# powerCard_rev0_1.net
KiCad netlist of a schematic drawn in EAGLE
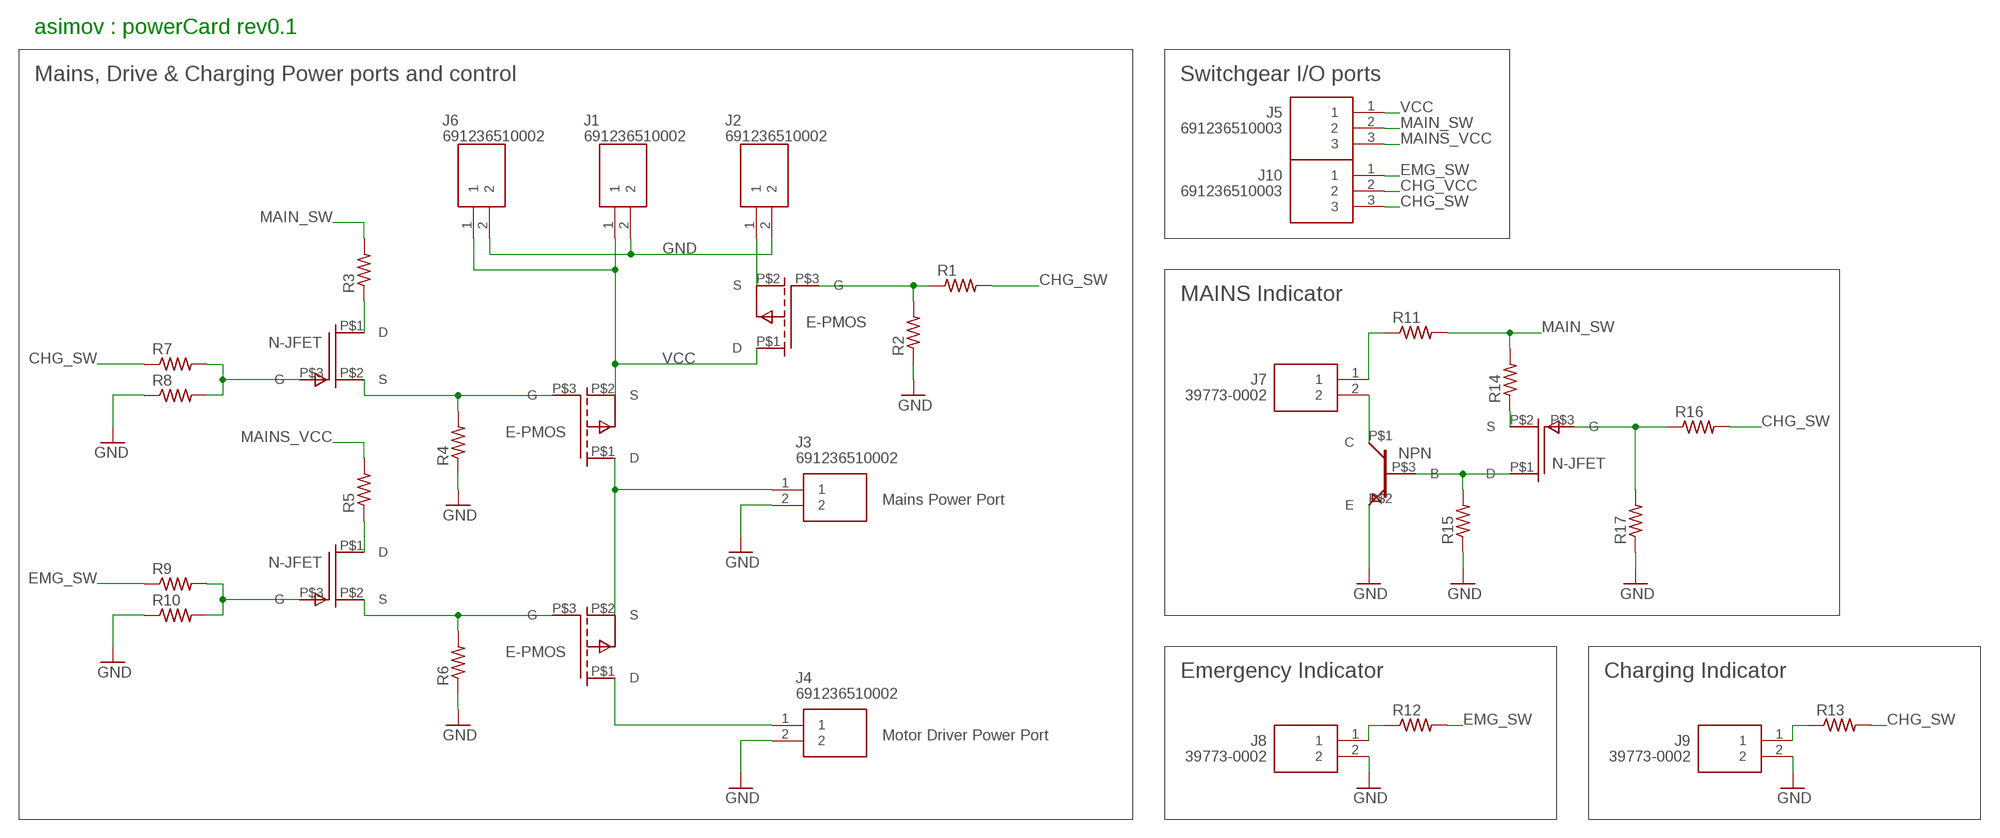
[diagram p0: schematic, sheet 1]

(export (version "E")
  (design (tool "Eeschema 10.0.6"))
  (components
    (comp (ref "J1")
      (value "691236510002")
      (footprint "eagle-import:SHDR2W90P0X508_1X2_1076X1135X1")
      (fields (field (name "MOUSER_PART_NUMBER") "710-691236510002"))
      (libsource (lib "eagle-import") (part "691236510002"))
    )
    (comp (ref "J2")
      (value "691236510002")
      (footprint "eagle-import:SHDR2W90P0X508_1X2_1076X1135X1")
      (fields (field (name "MOUSER_PART_NUMBER") "710-691236510002"))
      (libsource (lib "eagle-import") (part "691236510002"))
    )
    (comp (ref "J3")
      (value "691236510002")
      (footprint "eagle-import:SHDR2W90P0X508_1X2_1076X1135X1")
      (fields (field (name "MOUSER_PART_NUMBER") "710-691236510002"))
      (libsource (lib "eagle-import") (part "691236510002"))
    )
    (comp (ref "J4")
      (value "691236510002")
      (footprint "eagle-import:SHDR2W90P0X508_1X2_1076X1135X1")
      (fields (field (name "MOUSER_PART_NUMBER") "710-691236510002"))
      (libsource (lib "eagle-import") (part "691236510002"))
    )
    (comp (ref "J5")
      (value "691236510003")
      (footprint "eagle-import:SHDR3W90P0X508_1X3_1524X1135X1")
      (fields (field (name "MOUSER_PART_NUMBER") "710-691236510003"))
      (libsource (lib "eagle-import") (part "691236510003"))
    )
    (comp (ref "J6")
      (value "691236510002")
      (footprint "eagle-import:SHDR2W90P0X508_1X2_1076X1135X1")
      (fields (field (name "MOUSER_PART_NUMBER") "710-691236510002"))
      (libsource (lib "eagle-import") (part "691236510002"))
    )
    (comp (ref "J7")
      (value "39773-0002")
      (footprint "eagle-import:SHDR2W110P0X254_1X2_554X650X10")
      (fields (field (name "MOUSER_PART_NUMBER") "538-39773-0002"))
      (libsource (lib "eagle-import") (part "39773-0002"))
    )
    (comp (ref "J8")
      (value "39773-0002")
      (footprint "eagle-import:SHDR2W110P0X254_1X2_554X650X10")
      (fields (field (name "MOUSER_PART_NUMBER") "538-39773-0002"))
      (libsource (lib "eagle-import") (part "39773-0002"))
    )
    (comp (ref "J9")
      (value "39773-0002")
      (footprint "eagle-import:SHDR2W110P0X254_1X2_554X650X10")
      (fields (field (name "MOUSER_PART_NUMBER") "538-39773-0002"))
      (libsource (lib "eagle-import") (part "39773-0002"))
    )
    (comp (ref "J10")
      (value "691236510003")
      (footprint "eagle-import:SHDR3W90P0X508_1X3_1524X1135X1")
      (fields (field (name "MOUSER_PART_NUMBER") "710-691236510003"))
      (libsource (lib "eagle-import") (part "691236510003"))
    )
    (comp (ref "R1")
      (value "R-US_0204/7")
      (footprint "eagle-import:0204_7")
      (libsource (lib "eagle-import") (part "R-US_0204/7"))
    )
    (comp (ref "R2")
      (value "R-US_0204/7")
      (footprint "eagle-import:0204_7")
      (libsource (lib "eagle-import") (part "R-US_0204/7"))
    )
    (comp (ref "R3")
      (value "R-US_0204/7")
      (footprint "eagle-import:0204_7")
      (libsource (lib "eagle-import") (part "R-US_0204/7"))
    )
    (comp (ref "R4")
      (value "R-US_0204/7")
      (footprint "eagle-import:0204_7")
      (libsource (lib "eagle-import") (part "R-US_0204/7"))
    )
    (comp (ref "R5")
      (value "R-US_0204/7")
      (footprint "eagle-import:0204_7")
      (libsource (lib "eagle-import") (part "R-US_0204/7"))
    )
    (comp (ref "R6")
      (value "R-US_0204/7")
      (footprint "eagle-import:0204_7")
      (libsource (lib "eagle-import") (part "R-US_0204/7"))
    )
    (comp (ref "R7")
      (value "R-US_0204/7")
      (footprint "eagle-import:0204_7")
      (libsource (lib "eagle-import") (part "R-US_0204/7"))
    )
    (comp (ref "R8")
      (value "R-US_0204/7")
      (footprint "eagle-import:0204_7")
      (libsource (lib "eagle-import") (part "R-US_0204/7"))
    )
    (comp (ref "R9")
      (value "R-US_0204/7")
      (footprint "eagle-import:0204_7")
      (libsource (lib "eagle-import") (part "R-US_0204/7"))
    )
    (comp (ref "R10")
      (value "R-US_0204/7")
      (footprint "eagle-import:0204_7")
      (libsource (lib "eagle-import") (part "R-US_0204/7"))
    )
    (comp (ref "R11")
      (value "R-US_0204/7")
      (footprint "eagle-import:0204_7")
      (libsource (lib "eagle-import") (part "R-US_0204/7"))
    )
    (comp (ref "R12")
      (value "R-US_0204/7")
      (footprint "eagle-import:0204_7")
      (libsource (lib "eagle-import") (part "R-US_0204/7"))
    )
    (comp (ref "R13")
      (value "R-US_0204/7")
      (footprint "eagle-import:0204_7")
      (libsource (lib "eagle-import") (part "R-US_0204/7"))
    )
    (comp (ref "R14")
      (value "R-US_0204/7")
      (footprint "eagle-import:0204_7")
      (libsource (lib "eagle-import") (part "R-US_0204/7"))
    )
    (comp (ref "R15")
      (value "R-US_0204/7")
      (footprint "eagle-import:0204_7")
      (libsource (lib "eagle-import") (part "R-US_0204/7"))
    )
    (comp (ref "R16")
      (value "R-US_0204/7")
      (footprint "eagle-import:0204_7")
      (libsource (lib "eagle-import") (part "R-US_0204/7"))
    )
    (comp (ref "R17")
      (value "R-US_0204/7")
      (footprint "eagle-import:0204_7")
      (libsource (lib "eagle-import") (part "R-US_0204/7"))
    )
    (comp (ref "U$1")
      (value "E-PMOSFET")
      (footprint "eagle-import:TO-220")
      (libsource (lib "eagle-import") (part "E-PMOSFET"))
    )
    (comp (ref "U$2")
      (value "E-PMOSFET")
      (footprint "eagle-import:TO-220")
      (libsource (lib "eagle-import") (part "E-PMOSFET"))
    )
    (comp (ref "U$3")
      (value "E-PMOSFET")
      (footprint "eagle-import:TO-220")
      (libsource (lib "eagle-import") (part "E-PMOSFET"))
    )
    (comp (ref "U$4")
      (value "N-JFET")
      (footprint "eagle-import:TO-92(3L)")
      (libsource (lib "eagle-import") (part "N-JFET"))
    )
    (comp (ref "U$5")
      (value "N-JFET")
      (footprint "eagle-import:TO-92(3L)")
      (libsource (lib "eagle-import") (part "N-JFET"))
    )
    (comp (ref "U$6")
      (value "NPN-BJT")
      (footprint "eagle-import:TO-92")
      (libsource (lib "eagle-import") (part "NPN-BJT"))
    )
    (comp (ref "U$7")
      (value "N-JFET")
      (footprint "eagle-import:TO-92(3L)")
      (libsource (lib "eagle-import") (part "N-JFET"))
    )
  )
  (nets
    (net (code "1") (name "/CHG_SW") (class "Default")
      (node (ref "J10") (pin "3") (pinfunction "3_3") (pintype "bidirectional"))
      (node (ref "R1") (pin "2") (pinfunction "2_2") (pintype "passive"))
      (node (ref "R13") (pin "2") (pinfunction "2_2") (pintype "passive"))
      (node (ref "R16") (pin "2") (pinfunction "2_2") (pintype "passive"))
      (node (ref "R7") (pin "1") (pinfunction "1_1") (pintype "passive"))
    )
    (net (code "2") (name "/CHG_VCC") (class "Default")
      (node (ref "J10") (pin "2") (pinfunction "2_2") (pintype "bidirectional"))
      (node (ref "J2") (pin "1") (pinfunction "1_1") (pintype "bidirectional"))
      (node (ref "U$1") (pin "P$2") (pinfunction "S_P$2") (pintype "output"))
    )
    (net (code "3") (name "/EMG_SW") (class "Default")
      (node (ref "J10") (pin "1") (pinfunction "1_1") (pintype "bidirectional"))
      (node (ref "R12") (pin "2") (pinfunction "2_2") (pintype "passive"))
      (node (ref "R9") (pin "1") (pinfunction "1_1") (pintype "passive"))
    )
    (net (code "4") (name "/MAINS_VCC") (class "Default")
      (node (ref "J3") (pin "1") (pinfunction "1_1") (pintype "bidirectional"))
      (node (ref "J5") (pin "3") (pinfunction "3_3") (pintype "bidirectional"))
      (node (ref "R5") (pin "2") (pinfunction "2_2") (pintype "passive"))
      (node (ref "U$2") (pin "P$1") (pinfunction "D_P$1") (pintype "input"))
      (node (ref "U$3") (pin "P$2") (pinfunction "S_P$2") (pintype "output"))
    )
    (net (code "5") (name "/MAIN_SW") (class "Default")
      (node (ref "J5") (pin "2") (pinfunction "2_2") (pintype "bidirectional"))
      (node (ref "R11") (pin "2") (pinfunction "2_2") (pintype "passive"))
      (node (ref "R14") (pin "2") (pinfunction "2_2") (pintype "passive"))
      (node (ref "R3") (pin "2") (pinfunction "2_2") (pintype "passive"))
    )
    (net (code "6") (name "/VCC") (class "Default")
      (node (ref "J1") (pin "1") (pinfunction "1_1") (pintype "bidirectional"))
      (node (ref "J5") (pin "1") (pinfunction "1_1") (pintype "bidirectional"))
      (node (ref "J6") (pin "1") (pinfunction "1_1") (pintype "bidirectional"))
      (node (ref "U$1") (pin "P$1") (pinfunction "D_P$1") (pintype "input"))
      (node (ref "U$2") (pin "P$2") (pinfunction "S_P$2") (pintype "output"))
    )
    (net (code "7") (name "GND") (class "Default")
      (node (ref "J1") (pin "2") (pinfunction "2_2") (pintype "bidirectional"))
      (node (ref "J2") (pin "2") (pinfunction "2_2") (pintype "bidirectional"))
      (node (ref "J3") (pin "2") (pinfunction "2_2") (pintype "bidirectional"))
      (node (ref "J4") (pin "2") (pinfunction "2_2") (pintype "bidirectional"))
      (node (ref "J6") (pin "2") (pinfunction "2_2") (pintype "bidirectional"))
      (node (ref "J8") (pin "2") (pinfunction "2_2") (pintype "bidirectional"))
      (node (ref "J9") (pin "2") (pinfunction "2_2") (pintype "bidirectional"))
      (node (ref "R10") (pin "1") (pinfunction "1_1") (pintype "passive"))
      (node (ref "R15") (pin "1") (pinfunction "1_1") (pintype "passive"))
      (node (ref "R17") (pin "1") (pinfunction "1_1") (pintype "passive"))
      (node (ref "R2") (pin "1") (pinfunction "1_1") (pintype "passive"))
      (node (ref "R4") (pin "1") (pinfunction "1_1") (pintype "passive"))
      (node (ref "R6") (pin "1") (pinfunction "1_1") (pintype "passive"))
      (node (ref "R8") (pin "1") (pinfunction "1_1") (pintype "passive"))
      (node (ref "U$6") (pin "P$2") (pinfunction "E_P$2") (pintype "bidirectional"))
    )
    (net (code "8") (name "Net-(J7-Pad1)") (class "Default")
      (node (ref "J7") (pin "1") (pinfunction "1_1") (pintype "bidirectional"))
      (node (ref "R11") (pin "1") (pinfunction "1_1") (pintype "passive"))
    )
    (net (code "9") (name "Net-(J8-Pad1)") (class "Default")
      (node (ref "J8") (pin "1") (pinfunction "1_1") (pintype "bidirectional"))
      (node (ref "R12") (pin "1") (pinfunction "1_1") (pintype "passive"))
    )
    (net (code "10") (name "Net-(J9-Pad1)") (class "Default")
      (node (ref "J9") (pin "1") (pinfunction "1_1") (pintype "bidirectional"))
      (node (ref "R13") (pin "1") (pinfunction "1_1") (pintype "passive"))
    )
    (net (code "11") (name "Net-(U$1-G)") (class "Default")
      (node (ref "R1") (pin "1") (pinfunction "1_1") (pintype "passive"))
      (node (ref "R2") (pin "2") (pinfunction "2_2") (pintype "passive"))
      (node (ref "U$1") (pin "P$3") (pinfunction "G_P$3") (pintype "input"))
    )
    (net (code "12") (name "Net-(U$2-G)") (class "Default")
      (node (ref "R4") (pin "2") (pinfunction "2_2") (pintype "passive"))
      (node (ref "U$2") (pin "P$3") (pinfunction "G_P$3") (pintype "input"))
      (node (ref "U$4") (pin "P$2") (pinfunction "S_P$2") (pintype "output"))
    )
    (net (code "13") (name "Net-(U$3-D)") (class "Default")
      (node (ref "J4") (pin "1") (pinfunction "1_1") (pintype "bidirectional"))
      (node (ref "U$3") (pin "P$1") (pinfunction "D_P$1") (pintype "input"))
    )
    (net (code "14") (name "Net-(U$3-G)") (class "Default")
      (node (ref "R6") (pin "2") (pinfunction "2_2") (pintype "passive"))
      (node (ref "U$3") (pin "P$3") (pinfunction "G_P$3") (pintype "input"))
      (node (ref "U$5") (pin "P$2") (pinfunction "S_P$2") (pintype "output"))
    )
    (net (code "15") (name "Net-(U$4-D)") (class "Default")
      (node (ref "R3") (pin "1") (pinfunction "1_1") (pintype "passive"))
      (node (ref "U$4") (pin "P$1") (pinfunction "D_P$1") (pintype "input"))
    )
    (net (code "16") (name "Net-(U$4-G)") (class "Default")
      (node (ref "R7") (pin "2") (pinfunction "2_2") (pintype "passive"))
      (node (ref "R8") (pin "2") (pinfunction "2_2") (pintype "passive"))
      (node (ref "U$4") (pin "P$3") (pinfunction "G_P$3") (pintype "input"))
    )
    (net (code "17") (name "Net-(U$5-D)") (class "Default")
      (node (ref "R5") (pin "1") (pinfunction "1_1") (pintype "passive"))
      (node (ref "U$5") (pin "P$1") (pinfunction "D_P$1") (pintype "input"))
    )
    (net (code "18") (name "Net-(U$5-G)") (class "Default")
      (node (ref "R10") (pin "2") (pinfunction "2_2") (pintype "passive"))
      (node (ref "R9") (pin "2") (pinfunction "2_2") (pintype "passive"))
      (node (ref "U$5") (pin "P$3") (pinfunction "G_P$3") (pintype "input"))
    )
    (net (code "19") (name "Net-(U$6-B)") (class "Default")
      (node (ref "R15") (pin "2") (pinfunction "2_2") (pintype "passive"))
      (node (ref "U$6") (pin "P$3") (pinfunction "B_P$3") (pintype "bidirectional"))
      (node (ref "U$7") (pin "P$1") (pinfunction "D_P$1") (pintype "input"))
    )
    (net (code "20") (name "Net-(U$6-C)") (class "Default")
      (node (ref "J7") (pin "2") (pinfunction "2_2") (pintype "bidirectional"))
      (node (ref "U$6") (pin "P$1") (pinfunction "C_P$1") (pintype "bidirectional"))
    )
    (net (code "21") (name "Net-(U$7-G)") (class "Default")
      (node (ref "R16") (pin "1") (pinfunction "1_1") (pintype "passive"))
      (node (ref "R17") (pin "2") (pinfunction "2_2") (pintype "passive"))
      (node (ref "U$7") (pin "P$3") (pinfunction "G_P$3") (pintype "input"))
    )
    (net (code "22") (name "Net-(U$7-S)") (class "Default")
      (node (ref "R14") (pin "1") (pinfunction "1_1") (pintype "passive"))
      (node (ref "U$7") (pin "P$2") (pinfunction "S_P$2") (pintype "output"))
    )
  )
)
